# 2_-_MCU.net
KiCad netlist of a schematic drawn in Altium Designer
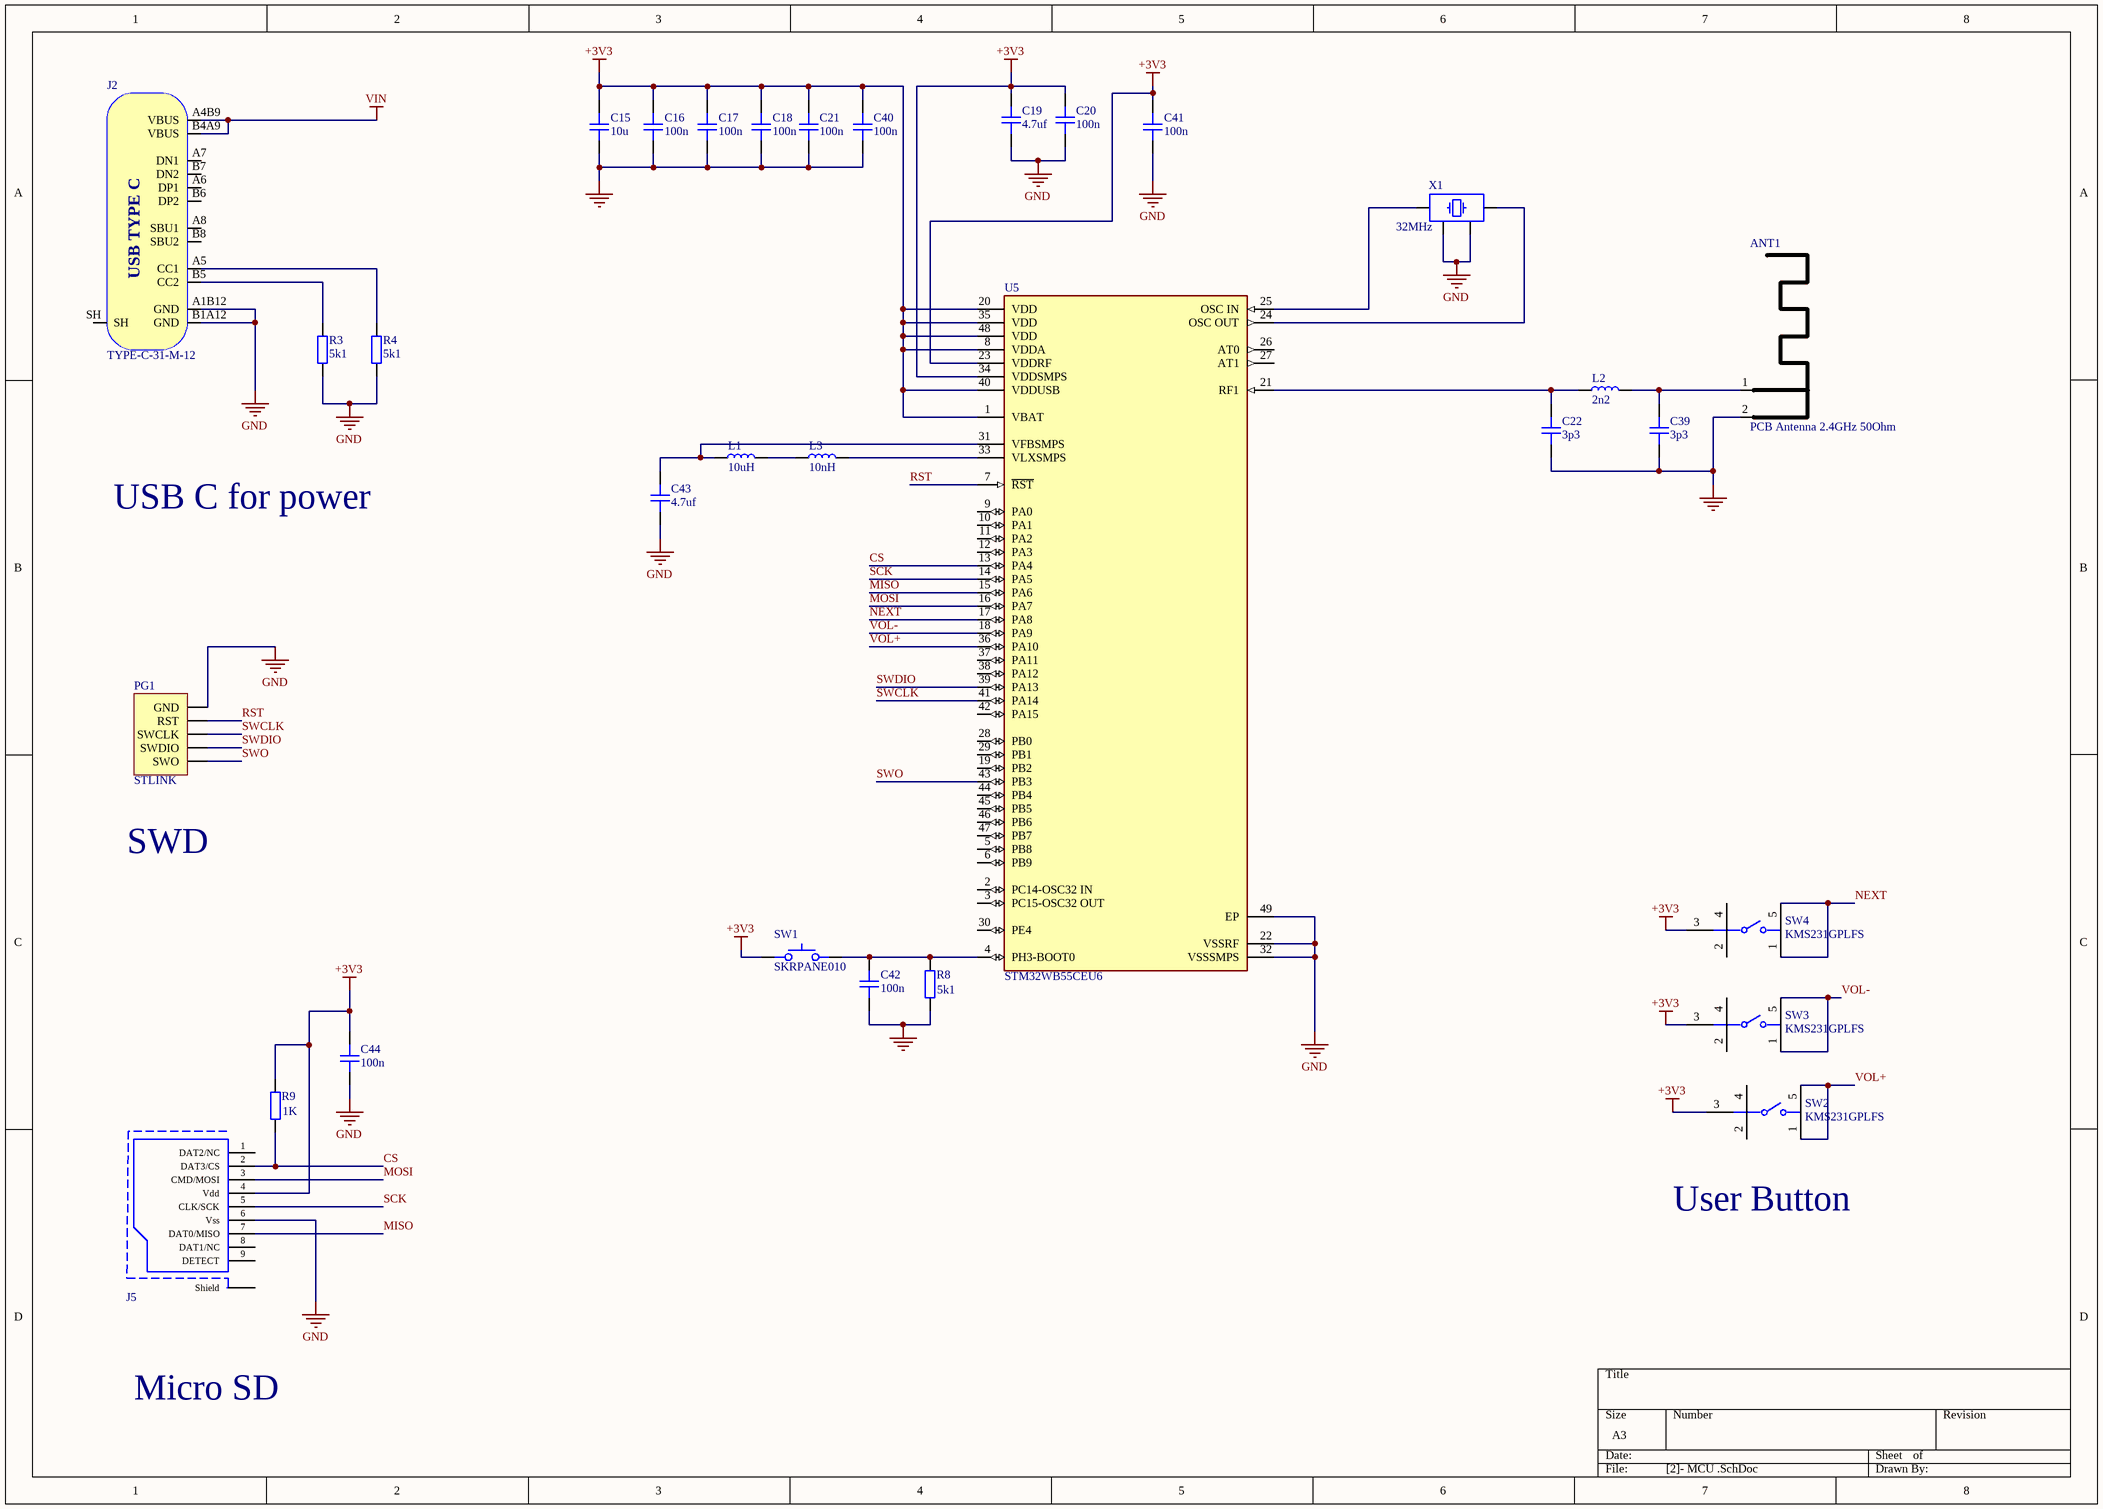
[diagram p0: [2]- MCU .SchDoc]

(export (version "E")
  (design (tool "Eeschema 10.0.6"))
  (components
    (comp (ref "ANT1")
      (value "PCB Antenna 2.4GHz 50Ohm")
      (footprint "ANT_IFA_USB_2_4GHZ_50R")
      (description "Inverted F 2.4GHz ISM PCB Antenna 50 Ohm")
      (libsource (lib "Schematic-Lib-PhilsLab") (part "ANT_IFA_USB_2_4GHZ_50R"))
    )
    (comp (ref "C15")
      (value "10u")
      (footprint "CAP_0603")
      (description "Capacitor SMD 0603 10V")
      (fields
        (field (name "MANUFACTURER") "Samsung")
        (field (name "MANUFACTURER PART NUMBER") "CL10A106KP8NNNC")
      )
      (libsource (lib "Schematic-Lib-PhilsLab") (part "CAP_0603_10V"))
    )
    (comp (ref "C16")
      (value "100n")
      (footprint "CAP_0402")
      (description "Capacitor SMD 0402 50V")
      (fields
        (field (name "MANUFACTURER") "Samsung")
        (field (name "MANUFACTURER PART NUMBER") "CL05B104KO5NNNC")
      )
      (libsource (lib "Schematic-Lib-PhilsLab") (part "CAP_0402_50V"))
    )
    (comp (ref "C17")
      (value "100n")
      (footprint "CAP_0402")
      (description "Capacitor SMD 0402 50V")
      (fields
        (field (name "MANUFACTURER") "Samsung")
        (field (name "MANUFACTURER PART NUMBER") "CL05B104KO5NNNC")
      )
      (libsource (lib "Schematic-Lib-PhilsLab") (part "CAP_0402_50V"))
    )
    (comp (ref "C18")
      (value "100n")
      (footprint "CAP_0402")
      (description "Capacitor SMD 0402 50V")
      (fields
        (field (name "MANUFACTURER") "Samsung")
        (field (name "MANUFACTURER PART NUMBER") "CL05B104KO5NNNC")
      )
      (libsource (lib "Schematic-Lib-PhilsLab") (part "CAP_0402_50V"))
    )
    (comp (ref "C19")
      (value "4.7uf")
      (footprint "CAP_0402")
      (description "Capacitor SMD 0402 50V")
      (fields (field (name "MANUFACTURER") "FH") (field (name "MANUFACTURER PART NUMBER") "0402CG3R3C500NT"))
      (libsource (lib "Schematic-Lib-PhilsLab") (part "CAP_0402_50V"))
    )
    (comp (ref "C20")
      (value "100n")
      (footprint "CAP_0402")
      (description "Capacitor SMD 0402 50V")
      (fields
        (field (name "MANUFACTURER") "Samsung")
        (field (name "MANUFACTURER PART NUMBER") "CL05B104KO5NNNC")
      )
      (libsource (lib "Schematic-Lib-PhilsLab") (part "CAP_0402_50V"))
    )
    (comp (ref "C21")
      (value "100n")
      (footprint "CAP_0402")
      (description "Capacitor SMD 0402 50V")
      (fields
        (field (name "MANUFACTURER") "Samsung")
        (field (name "MANUFACTURER PART NUMBER") "CL05B104KO5NNNC")
      )
      (libsource (lib "Schematic-Lib-PhilsLab") (part "CAP_0402_50V"))
    )
    (comp (ref "C22")
      (value "3p3")
      (footprint "CAP_0402")
      (description "Capacitor SMD 0402 50V")
      (fields (field (name "MANUFACTURER") "FH") (field (name "MANUFACTURER PART NUMBER") "0402CG3R3C500NT"))
      (libsource (lib "Schematic-Lib-PhilsLab") (part "CAP_0402_50V"))
    )
    (comp (ref "C39")
      (value "3p3")
      (footprint "CAP_0402")
      (description "Capacitor SMD 0402 50V")
      (fields (field (name "MANUFACTURER") "FH") (field (name "MANUFACTURER PART NUMBER") "0402CG3R3C500NT"))
      (libsource (lib "Schematic-Lib-PhilsLab") (part "CAP_0402_50V"))
    )
    (comp (ref "C40")
      (value "100n")
      (footprint "CAP_0402")
      (description "Capacitor SMD 0402 50V")
      (fields
        (field (name "MANUFACTURER") "Samsung")
        (field (name "MANUFACTURER PART NUMBER") "CL05B104KO5NNNC")
      )
      (libsource (lib "Schematic-Lib-PhilsLab") (part "CAP_0402_50V"))
    )
    (comp (ref "C41")
      (value "100n")
      (footprint "CAP_0402")
      (description "Capacitor SMD 0402 50V")
      (fields
        (field (name "MANUFACTURER") "Samsung")
        (field (name "MANUFACTURER PART NUMBER") "CL05B104KO5NNNC")
      )
      (libsource (lib "Schematic-Lib-PhilsLab") (part "CAP_0402_50V"))
    )
    (comp (ref "C42")
      (value "100n")
      (footprint "CAP_0402")
      (description "Capacitor SMD 0402 50V")
      (fields
        (field (name "MANUFACTURER") "Samsung")
        (field (name "MANUFACTURER PART NUMBER") "CL05B104KO5NNNC")
      )
      (libsource (lib "Schematic-Lib-PhilsLab") (part "CAP_0402_50V"))
    )
    (comp (ref "C43")
      (value "4.7uf")
      (footprint "CAP_0603")
      (description "Capacitor SMD 0603 10V")
      (fields
        (field (name "MANUFACTURER") "Samsung")
        (field (name "MANUFACTURER PART NUMBER") "CL10A106KP8NNNC")
      )
      (libsource (lib "Schematic-Lib-PhilsLab") (part "CAP_0603_10V"))
    )
    (comp (ref "C44")
      (value "100n")
      (footprint "CAP_0402")
      (description "Capacitor SMD 0402 50V")
      (fields
        (field (name "MANUFACTURER") "Samsung")
        (field (name "MANUFACTURER PART NUMBER") "CL05B104KO5NNNC")
      )
      (libsource (lib "Schematic-Lib-PhilsLab") (part "CAP_0402_50V"))
    )
    (comp (ref "J2")
      (value "TYPE-C-31-M-12")
      (footprint "TYPE-C-31-M-12")
      (description "USB Type C Connector Horizontal SMT")
      (fields (field (name "MANUFACTURER") "Koren Hroparts"))
      (libsource (lib "ESP32_USB_Dongle") (part "TYPE-C-31-M-12"))
    )
    (comp (ref "J5")
      (value "Micro SD")
      (footprint "TFP-09-2-12B")
      (fields (field (name "PARTNUMBER") "TFP-09-2-12B"))
      (libsource (lib "Conn Card") (part "Micro SD TFP-09-2-12B"))
    )
    (comp (ref "L1")
      (value "10uH")
      (footprint "IND_0402")
      (description "Inductor SMD 0402")
      (fields
        (field (name "MANUFACTURER") "Murata")
        (field (name "MANUFACTURER PART NUMBER") "LQW15AN2N2G80D")
      )
      (libsource (lib "Schematic-Lib-PhilsLab") (part "IND_0402"))
    )
    (comp (ref "L2")
      (value "2n2")
      (footprint "IND_0402")
      (description "Inductor SMD 0402")
      (fields
        (field (name "MANUFACTURER") "Murata")
        (field (name "MANUFACTURER PART NUMBER") "LQW15AN2N2G80D")
      )
      (libsource (lib "Schematic-Lib-PhilsLab") (part "IND_0402"))
    )
    (comp (ref "L3")
      (value "10nH")
      (footprint "IND_0402")
      (description "Inductor SMD 0402")
      (fields
        (field (name "MANUFACTURER") "Murata")
        (field (name "MANUFACTURER PART NUMBER") "LQW15AN2N2G80D")
      )
      (libsource (lib "Schematic-Lib-PhilsLab") (part "IND_0402"))
    )
    (comp (ref "PG1")
      (value "STLINK")
      (footprint "HDR_M_1X5")
      (fields (field (name "PARTNUMBER") "Header 1X5 P2.54mm"))
      (libsource (lib "Conn Programmer") (part "STLINK Header P2.54mm (THD)"))
    )
    (comp (ref "R3")
      (value "5k1")
      (footprint "RES_0402")
      (description "Resistor SMD 0402")
      (fields
        (field (name "MANUFACTURER") "YAGEO")
        (field (name "MANUFACTURER PART NUMBER") "RC0402JR-075K1L")
      )
      (libsource (lib "ESP32_USB_Dongle") (part "RES_0402"))
    )
    (comp (ref "R4")
      (value "5k1")
      (footprint "RES_0402")
      (description "Resistor SMD 0402")
      (fields
        (field (name "MANUFACTURER") "YAGEO")
        (field (name "MANUFACTURER PART NUMBER") "RC0402JR-075K1L")
      )
      (libsource (lib "ESP32_USB_Dongle") (part "RES_0402"))
    )
    (comp (ref "R8")
      (value "5k1")
      (footprint "RES_0402")
      (description "Resistor SMD 0402")
      (fields
        (field (name "MANUFACTURER") "YAGEO")
        (field (name "MANUFACTURER PART NUMBER") "RC0402JR-075K1L")
      )
      (libsource (lib "Schematic-Lib-PhilsLab") (part "RES_0402"))
    )
    (comp (ref "R9")
      (value "1K")
      (footprint "RES_0402")
      (description "Resistor SMD 0402")
      (fields
        (field (name "MANUFACTURER") "YAGEO")
        (field (name "MANUFACTURER PART NUMBER") "RC0402JR-075K1L")
      )
      (libsource (lib "Schematic-Lib-PhilsLab") (part "RES_0402"))
    )
    (comp (ref "SW1")
      (value "SKRPANE010")
      (footprint "SKRPANE010")
      (description "Tactile Switch SMD SPST")
      (fields (field (name "MANUFACTURER") "Alps Alpine"))
      (libsource (lib "Schematic-Lib-PhilsLab") (part "SKRPANE010"))
    )
    (comp (ref "SW2")
      (value "KMS231GPLFS")
      (footprint "FP-KMS231GPLFS-MFG")
      (description "SWITCH TACTILE SPST-NO 0.05A 50V")
      (libsource (lib "Altium Content Vault") (part "96206a584fada216e410b81990591b9"))
    )
    (comp (ref "SW3")
      (value "KMS231GPLFS")
      (footprint "FP-KMS231GPLFS-MFG")
      (description "SWITCH TACTILE SPST-NO 0.05A 50V")
      (libsource (lib "Altium Content Vault") (part "96206a584fada216e410b81990591b9"))
    )
    (comp (ref "SW4")
      (value "KMS231GPLFS")
      (footprint "FP-KMS231GPLFS-MFG")
      (description "SWITCH TACTILE SPST-NO 0.05A 50V")
      (libsource (lib "Altium Content Vault") (part "96206a584fada216e410b81990591b9"))
    )
    (comp (ref "U5")
      (value "STM32WB55CEU6")
      (footprint "FP-UFQFPN48-A0B9-MFG")
      (description "ULTRA-LOW-POWER DUAL CORE ARM CO")
      (fields
        (field (name "MANUFACTURER") "STMicroelectronics")
        (field (name "OCTOPART") "https://octopart.com/stm32wb55ceu6-stmicroelectronics-96611730")
      )
      (libsource (lib "Altium Content Vault") (part "eb21ff5a47d2ca5be7d501793015931"))
    )
    (comp (ref "X1")
      (value "32MHz")
      (footprint "XTAL_2520")
      (description "Crystal SMD 2520")
      (fields (field (name "MANUFACTURER") "Seiko Epson"))
      (libsource (lib "ESP32_USB_Dongle") (part "XTAL_2520"))
    )
  )
  (nets
    (net (code "1") (name "+3V3") (class "Default")
      (node (ref "C15") (pin "2") (pinfunction "2_2") (pintype "passive"))
      (node (ref "C16") (pin "2") (pinfunction "2_2") (pintype "passive"))
      (node (ref "C17") (pin "2") (pinfunction "2_2") (pintype "passive"))
      (node (ref "C18") (pin "2") (pinfunction "2_2") (pintype "passive"))
      (node (ref "C19") (pin "2") (pinfunction "2_2") (pintype "passive"))
      (node (ref "C20") (pin "2") (pinfunction "2_2") (pintype "passive"))
      (node (ref "C21") (pin "2") (pinfunction "2_2") (pintype "passive"))
      (node (ref "C40") (pin "2") (pinfunction "2_2") (pintype "passive"))
      (node (ref "C41") (pin "2") (pinfunction "2_2") (pintype "passive"))
      (node (ref "C44") (pin "2") (pinfunction "2_2") (pintype "passive"))
      (node (ref "J5") (pin "4") (pinfunction "Vdd_4") (pintype "passive"))
      (node (ref "R9") (pin "2") (pinfunction "2_2") (pintype "passive"))
      (node (ref "SW1") (pin "34") (pintype "passive"))
      (node (ref "SW2") (pin "3") (pinfunction "3_3") (pintype "passive"))
      (node (ref "SW3") (pin "3") (pinfunction "3_3") (pintype "passive"))
      (node (ref "SW4") (pin "3") (pinfunction "3_3") (pintype "passive"))
      (node (ref "U5") (pin "1") (pinfunction "VBAT_1") (pintype "power_in"))
      (node (ref "U5") (pin "20") (pinfunction "VDD_20") (pintype "power_in"))
      (node (ref "U5") (pin "23") (pinfunction "VDDRF_23") (pintype "power_in"))
      (node (ref "U5") (pin "34") (pinfunction "VDDSMPS_34") (pintype "power_in"))
      (node (ref "U5") (pin "35") (pinfunction "VDD_35") (pintype "power_in"))
      (node (ref "U5") (pin "40") (pinfunction "VDDUSB_40") (pintype "power_in"))
      (node (ref "U5") (pin "48") (pinfunction "VDD_48") (pintype "power_in"))
      (node (ref "U5") (pin "8") (pinfunction "VDDA_8") (pintype "power_in"))
    )
    (net (code "2") (name "/CS") (class "Default")
      (node (ref "J5") (pin "2") (pinfunction "DAT3/CS_2") (pintype "passive"))
      (node (ref "R9") (pin "1") (pinfunction "1_1") (pintype "passive"))
      (node (ref "U5") (pin "13") (pinfunction "PA4_13") (pintype "bidirectional"))
    )
    (net (code "3") (name "/MISO") (class "Default")
      (node (ref "J5") (pin "7") (pinfunction "DAT0/MISO_7") (pintype "passive"))
      (node (ref "U5") (pin "15") (pinfunction "PA6_15") (pintype "bidirectional"))
    )
    (net (code "4") (name "/MOSI") (class "Default")
      (node (ref "J5") (pin "3") (pinfunction "CMD/MOSI_3") (pintype "passive"))
      (node (ref "U5") (pin "16") (pinfunction "PA7_16") (pintype "bidirectional"))
    )
    (net (code "5") (name "/NEXT") (class "Default")
      (node (ref "SW4") (pin "1") (pinfunction "1_1") (pintype "passive"))
      (node (ref "SW4") (pin "5") (pinfunction "5_5") (pintype "passive"))
      (node (ref "U5") (pin "17") (pinfunction "PA8_17") (pintype "bidirectional"))
    )
    (net (code "6") (name "/RST") (class "Default")
      (node (ref "PG1") (pin "2") (pinfunction "RST_2") (pintype "passive"))
      (node (ref "U5") (pin "7") (pinfunction "~{RST}_7") (pintype "input"))
    )
    (net (code "7") (name "/SCK") (class "Default")
      (node (ref "J5") (pin "5") (pinfunction "CLK/SCK_5") (pintype "passive"))
      (node (ref "U5") (pin "14") (pinfunction "PA5_14") (pintype "bidirectional"))
    )
    (net (code "8") (name "/SWCLK") (class "Default")
      (node (ref "PG1") (pin "3") (pinfunction "SWCLK_3") (pintype "passive"))
      (node (ref "U5") (pin "41") (pinfunction "PA14_41") (pintype "bidirectional"))
    )
    (net (code "9") (name "/SWDIO") (class "Default")
      (node (ref "PG1") (pin "4") (pinfunction "SWDIO_4") (pintype "passive"))
      (node (ref "U5") (pin "39") (pinfunction "PA13_39") (pintype "bidirectional"))
    )
    (net (code "10") (name "/SWO") (class "Default")
      (node (ref "PG1") (pin "5") (pinfunction "SWO_5") (pintype "passive"))
      (node (ref "U5") (pin "43") (pinfunction "PB3_43") (pintype "bidirectional"))
    )
    (net (code "11") (name "/VOL+") (class "Default")
      (node (ref "SW2") (pin "1") (pinfunction "1_1") (pintype "passive"))
      (node (ref "SW2") (pin "5") (pinfunction "5_5") (pintype "passive"))
      (node (ref "U5") (pin "36") (pinfunction "PA10_36") (pintype "bidirectional"))
    )
    (net (code "12") (name "/VOL-") (class "Default")
      (node (ref "SW3") (pin "1") (pinfunction "1_1") (pintype "passive"))
      (node (ref "SW3") (pin "5") (pinfunction "5_5") (pintype "passive"))
      (node (ref "U5") (pin "18") (pinfunction "PA9_18") (pintype "bidirectional"))
    )
    (net (code "13") (name "GND") (class "Default")
      (node (ref "ANT1") (pin "2") (pinfunction "GND_2") (pintype "passive"))
      (node (ref "C15") (pin "1") (pinfunction "1_1") (pintype "passive"))
      (node (ref "C16") (pin "1") (pinfunction "1_1") (pintype "passive"))
      (node (ref "C17") (pin "1") (pinfunction "1_1") (pintype "passive"))
      (node (ref "C18") (pin "1") (pinfunction "1_1") (pintype "passive"))
      (node (ref "C19") (pin "1") (pinfunction "1_1") (pintype "passive"))
      (node (ref "C20") (pin "1") (pinfunction "1_1") (pintype "passive"))
      (node (ref "C21") (pin "1") (pinfunction "1_1") (pintype "passive"))
      (node (ref "C22") (pin "1") (pinfunction "1_1") (pintype "passive"))
      (node (ref "C39") (pin "1") (pinfunction "1_1") (pintype "passive"))
      (node (ref "C40") (pin "1") (pinfunction "1_1") (pintype "passive"))
      (node (ref "C41") (pin "1") (pinfunction "1_1") (pintype "passive"))
      (node (ref "C42") (pin "1") (pinfunction "1_1") (pintype "passive"))
      (node (ref "C43") (pin "1") (pinfunction "1_1") (pintype "passive"))
      (node (ref "C44") (pin "1") (pinfunction "1_1") (pintype "passive"))
      (node (ref "J2") (pin "A1B12") (pinfunction "GND_A1B12") (pintype "power_in"))
      (node (ref "J2") (pin "B1A12") (pinfunction "GND_B1A12") (pintype "power_in"))
      (node (ref "J5") (pin "6") (pinfunction "Vss_6") (pintype "passive"))
      (node (ref "PG1") (pin "1") (pinfunction "GND_1") (pintype "passive"))
      (node (ref "R3") (pin "1") (pinfunction "1_1") (pintype "passive"))
      (node (ref "R4") (pin "1") (pinfunction "1_1") (pintype "passive"))
      (node (ref "R8") (pin "1") (pinfunction "1_1") (pintype "passive"))
      (node (ref "U5") (pin "22") (pinfunction "VSSRF_22") (pintype "power_in"))
      (node (ref "U5") (pin "32") (pinfunction "VSSSMPS_32") (pintype "power_in"))
      (node (ref "U5") (pin "49") (pinfunction "EP_49") (pintype "power_in"))
      (node (ref "X1") (pin "2") (pinfunction "2_2") (pintype "passive"))
      (node (ref "X1") (pin "4") (pinfunction "4_4") (pintype "passive"))
    )
    (net (code "14") (name "Net-(ANT1-RF)") (class "Default")
      (node (ref "ANT1") (pin "1") (pinfunction "RF_1") (pintype "passive"))
      (node (ref "C39") (pin "2") (pinfunction "2_2") (pintype "passive"))
      (node (ref "L2") (pin "1") (pinfunction "1_1") (pintype "passive"))
    )
    (net (code "15") (name "Net-(J2-CC1)") (class "Default")
      (node (ref "J2") (pin "A5") (pinfunction "CC1_A5") (pintype "passive"))
      (node (ref "R4") (pin "2") (pinfunction "2_2") (pintype "passive"))
    )
    (net (code "16") (name "Net-(J2-CC2)") (class "Default")
      (node (ref "J2") (pin "B5") (pinfunction "CC2_B5") (pintype "tri_state"))
      (node (ref "R3") (pin "2") (pinfunction "2_2") (pintype "passive"))
    )
    (net (code "17") (name "Net-(L1-Pad1)") (class "Default")
      (node (ref "L1") (pin "1") (pinfunction "1_1") (pintype "passive"))
      (node (ref "L3") (pin "2") (pinfunction "2_2") (pintype "passive"))
    )
    (net (code "18") (name "Net-(U5-OSC_IN)") (class "Default")
      (node (ref "U5") (pin "25") (pinfunction "OSC_IN_25") (pintype "input"))
      (node (ref "X1") (pin "1") (pinfunction "1_1") (pintype "passive"))
    )
    (net (code "19") (name "Net-(U5-OSC_OUT)") (class "Default")
      (node (ref "U5") (pin "24") (pinfunction "OSC_OUT_24") (pintype "output"))
      (node (ref "X1") (pin "3") (pinfunction "3_3") (pintype "passive"))
    )
    (net (code "20") (name "Net-(U5-PH3-BOOT0)") (class "Default")
      (node (ref "C42") (pin "2") (pinfunction "2_2") (pintype "passive"))
      (node (ref "R8") (pin "2") (pinfunction "2_2") (pintype "passive"))
      (node (ref "SW1") (pin "12") (pintype "passive"))
      (node (ref "U5") (pin "4") (pinfunction "PH3-BOOT0_4") (pintype "bidirectional"))
    )
    (net (code "21") (name "Net-(U5-RF1)") (class "Default")
      (node (ref "C22") (pin "2") (pinfunction "2_2") (pintype "passive"))
      (node (ref "L2") (pin "2") (pinfunction "2_2") (pintype "passive"))
      (node (ref "U5") (pin "21") (pinfunction "RF1_21") (pintype "input"))
    )
    (net (code "22") (name "Net-(U5-VFBSMPS)") (class "Default")
      (node (ref "C43") (pin "2") (pinfunction "2_2") (pintype "passive"))
      (node (ref "L1") (pin "2") (pinfunction "2_2") (pintype "passive"))
      (node (ref "U5") (pin "31") (pinfunction "VFBSMPS_31") (pintype "power_in"))
    )
    (net (code "23") (name "Net-(U5-VLXSMPS)") (class "Default")
      (node (ref "L3") (pin "1") (pinfunction "1_1") (pintype "passive"))
      (node (ref "U5") (pin "33") (pinfunction "VLXSMPS_33") (pintype "power_in"))
    )
    (net (code "24") (name "VIN") (class "Default")
      (node (ref "J2") (pin "A4B9") (pinfunction "VBUS_A4B9") (pintype "power_in"))
      (node (ref "J2") (pin "B4A9") (pinfunction "VBUS_B4A9") (pintype "power_in"))
    )
    (net (code "25") (name "unconnected-(J2-DN1-PadA7)") (class "Default")
      (node (ref "J2") (pin "A7") (pinfunction "DN1_A7") (pintype "bidirectional"))
    )
    (net (code "26") (name "unconnected-(J2-DN2-PadB7)") (class "Default")
      (node (ref "J2") (pin "B7") (pinfunction "DN2_B7") (pintype "bidirectional"))
    )
    (net (code "27") (name "unconnected-(J2-DP1-PadA6)") (class "Default")
      (node (ref "J2") (pin "A6") (pinfunction "DP1_A6") (pintype "bidirectional"))
    )
    (net (code "28") (name "unconnected-(J2-DP2-PadB6)") (class "Default")
      (node (ref "J2") (pin "B6") (pinfunction "DP2_B6") (pintype "bidirectional"))
    )
    (net (code "29") (name "unconnected-(J2-PadSH)") (class "Default")
      (node (ref "J2") (pin "SH") (pinfunction "SH_SH") (pintype "power_in"))
    )
    (net (code "30") (name "unconnected-(J2-SBU1-PadA8)") (class "Default")
      (node (ref "J2") (pin "A8") (pinfunction "SBU1_A8") (pintype "bidirectional"))
    )
    (net (code "31") (name "unconnected-(J2-SBU2-PadB8)") (class "Default")
      (node (ref "J2") (pin "B8") (pinfunction "SBU2_B8") (pintype "bidirectional"))
    )
    (net (code "32") (name "unconnected-(J5-DAT1{slash}NC-Pad8)") (class "Default")
      (node (ref "J5") (pin "8") (pinfunction "DAT1/NC_8") (pintype "passive"))
    )
    (net (code "33") (name "unconnected-(J5-DAT2{slash}NC-Pad1)") (class "Default")
      (node (ref "J5") (pin "1") (pinfunction "DAT2/NC_1") (pintype "passive"))
    )
    (net (code "34") (name "unconnected-(J5-DETECT-Pad9)") (class "Default")
      (node (ref "J5") (pin "9") (pinfunction "DETECT_9") (pintype "passive"))
    )
    (net (code "35") (name "unconnected-(J5-Shield-Pad10)") (class "Default")
      (node (ref "J5") (pin "10") (pinfunction "Shield_10") (pintype "passive"))
    )
    (net (code "36") (name "unconnected-(SW2-Pad2)") (class "Default")
      (node (ref "SW2") (pin "2") (pinfunction "2_2") (pintype "passive"))
    )
    (net (code "37") (name "unconnected-(SW2-Pad4)") (class "Default")
      (node (ref "SW2") (pin "4") (pinfunction "4_4") (pintype "passive"))
    )
    (net (code "38") (name "unconnected-(SW3-Pad2)") (class "Default")
      (node (ref "SW3") (pin "2") (pinfunction "2_2") (pintype "passive"))
    )
    (net (code "39") (name "unconnected-(SW3-Pad4)") (class "Default")
      (node (ref "SW3") (pin "4") (pinfunction "4_4") (pintype "passive"))
    )
    (net (code "40") (name "unconnected-(SW4-Pad2)") (class "Default")
      (node (ref "SW4") (pin "2") (pinfunction "2_2") (pintype "passive"))
    )
    (net (code "41") (name "unconnected-(SW4-Pad4)") (class "Default")
      (node (ref "SW4") (pin "4") (pinfunction "4_4") (pintype "passive"))
    )
    (net (code "42") (name "unconnected-(U5-AT0-Pad26)") (class "Default")
      (node (ref "U5") (pin "26") (pinfunction "AT0_26") (pintype "output"))
    )
    (net (code "43") (name "unconnected-(U5-AT1-Pad27)") (class "Default")
      (node (ref "U5") (pin "27") (pinfunction "AT1_27") (pintype "output"))
    )
    (net (code "44") (name "unconnected-(U5-PA0-Pad9)") (class "Default")
      (node (ref "U5") (pin "9") (pinfunction "PA0_9") (pintype "bidirectional"))
    )
    (net (code "45") (name "unconnected-(U5-PA1-Pad10)") (class "Default")
      (node (ref "U5") (pin "10") (pinfunction "PA1_10") (pintype "bidirectional"))
    )
    (net (code "46") (name "unconnected-(U5-PA2-Pad11)") (class "Default")
      (node (ref "U5") (pin "11") (pinfunction "PA2_11") (pintype "bidirectional"))
    )
    (net (code "47") (name "unconnected-(U5-PA3-Pad12)") (class "Default")
      (node (ref "U5") (pin "12") (pinfunction "PA3_12") (pintype "bidirectional"))
    )
    (net (code "48") (name "unconnected-(U5-PA11-Pad37)") (class "Default")
      (node (ref "U5") (pin "37") (pinfunction "PA11_37") (pintype "bidirectional"))
    )
    (net (code "49") (name "unconnected-(U5-PA12-Pad38)") (class "Default")
      (node (ref "U5") (pin "38") (pinfunction "PA12_38") (pintype "bidirectional"))
    )
    (net (code "50") (name "unconnected-(U5-PA15-Pad42)") (class "Default")
      (node (ref "U5") (pin "42") (pinfunction "PA15_42") (pintype "bidirectional"))
    )
    (net (code "51") (name "unconnected-(U5-PB0-Pad28)") (class "Default")
      (node (ref "U5") (pin "28") (pinfunction "PB0_28") (pintype "bidirectional"))
    )
    (net (code "52") (name "unconnected-(U5-PB1-Pad29)") (class "Default")
      (node (ref "U5") (pin "29") (pinfunction "PB1_29") (pintype "bidirectional"))
    )
    (net (code "53") (name "unconnected-(U5-PB2-Pad19)") (class "Default")
      (node (ref "U5") (pin "19") (pinfunction "PB2_19") (pintype "bidirectional"))
    )
    (net (code "54") (name "unconnected-(U5-PB4-Pad44)") (class "Default")
      (node (ref "U5") (pin "44") (pinfunction "PB4_44") (pintype "bidirectional"))
    )
    (net (code "55") (name "unconnected-(U5-PB5-Pad45)") (class "Default")
      (node (ref "U5") (pin "45") (pinfunction "PB5_45") (pintype "bidirectional"))
    )
    (net (code "56") (name "unconnected-(U5-PB6-Pad46)") (class "Default")
      (node (ref "U5") (pin "46") (pinfunction "PB6_46") (pintype "bidirectional"))
    )
    (net (code "57") (name "unconnected-(U5-PB7-Pad47)") (class "Default")
      (node (ref "U5") (pin "47") (pinfunction "PB7_47") (pintype "bidirectional"))
    )
    (net (code "58") (name "unconnected-(U5-PB8-Pad5)") (class "Default")
      (node (ref "U5") (pin "5") (pinfunction "PB8_5") (pintype "bidirectional"))
    )
    (net (code "59") (name "unconnected-(U5-PB9-Pad6)") (class "Default")
      (node (ref "U5") (pin "6") (pinfunction "PB9_6") (pintype "bidirectional"))
    )
    (net (code "60") (name "unconnected-(U5-PC14-OSC32_IN-Pad2)") (class "Default")
      (node (ref "U5") (pin "2") (pinfunction "PC14-OSC32_IN_2") (pintype "bidirectional"))
    )
    (net (code "61") (name "unconnected-(U5-PC15-OSC32_OUT-Pad3)") (class "Default")
      (node (ref "U5") (pin "3") (pinfunction "PC15-OSC32_OUT_3") (pintype "bidirectional"))
    )
    (net (code "62") (name "unconnected-(U5-PE4-Pad30)") (class "Default")
      (node (ref "U5") (pin "30") (pinfunction "PE4_30") (pintype "bidirectional"))
    )
  )
)
